# 04-SPDIF_IIC.net
KiCad netlist of a schematic drawn in Altium Designer
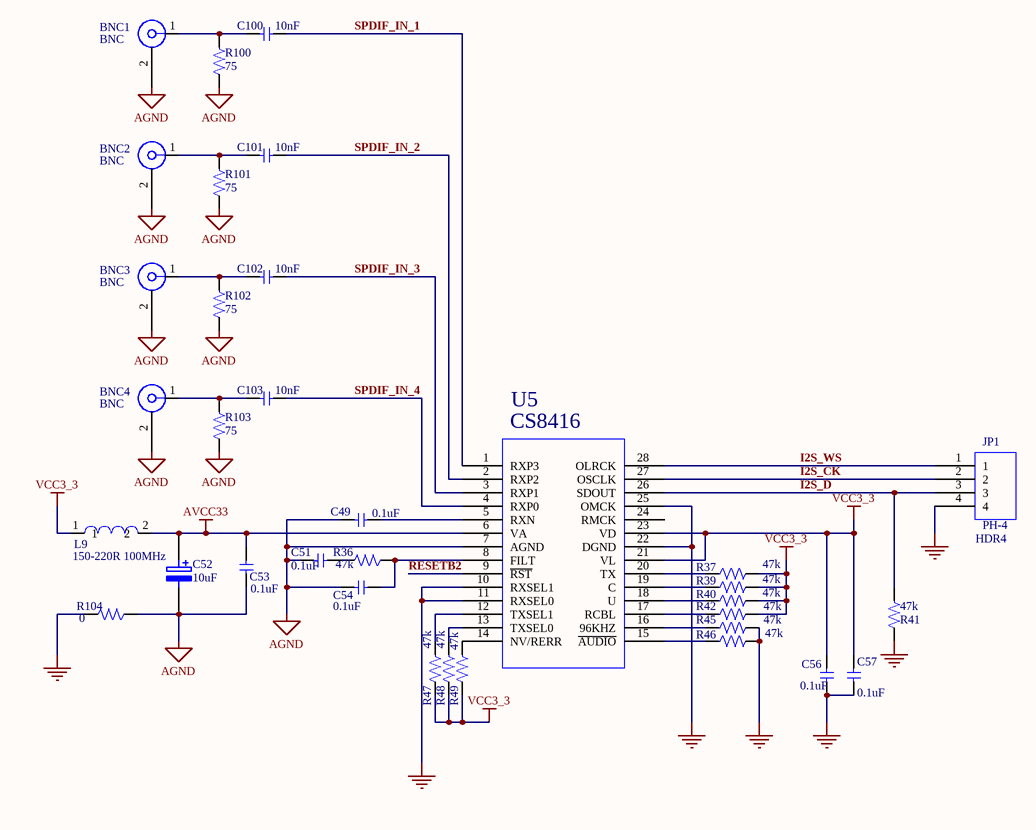
[diagram p0: 04-SPDIF_IIC.SchDoc]

(export (version "E")
  (design (tool "Eeschema 10.0.6"))
  (components
    (comp (ref "BNC1")
      (value "BNC")
      (footprint "RCA-101")
      (fields (field (name "SOURCE_PATH") "C:\\PROGRAM FILES\\印院出品\\CAPTURE 16.2\\LIBRARY\\CONNECTOR.OLB"))
      (libsource (lib "VIDEO_Demo_Kit_1") (part "BNC"))
    )
    (comp (ref "BNC2")
      (value "BNC")
      (footprint "RCA-101")
      (fields (field (name "SOURCE_PATH") "C:\\PROGRAM FILES\\印院出品\\CAPTURE 16.2\\LIBRARY\\CONNECTOR.OLB"))
      (libsource (lib "VIDEO_Demo_Kit_1") (part "BNC"))
    )
    (comp (ref "BNC3")
      (value "BNC")
      (footprint "RCA-101")
      (fields (field (name "SOURCE_PATH") "C:\\PROGRAM FILES\\印院出品\\CAPTURE 16.2\\LIBRARY\\CONNECTOR.OLB"))
      (libsource (lib "VIDEO_Demo_Kit_1") (part "BNC"))
    )
    (comp (ref "BNC4")
      (value "BNC")
      (footprint "RCA-101")
      (fields (field (name "SOURCE_PATH") "C:\\PROGRAM FILES\\印院出品\\CAPTURE 16.2\\LIBRARY\\CONNECTOR.OLB"))
      (libsource (lib "VIDEO_Demo_Kit_1") (part "BNC"))
    )
    (comp (ref "C49")
      (value "0.1uF")
      (footprint "C0603")
      (fields (field (name "VOLTAGE") "CMAX") (field (name "Comment") "C_2"))
      (libsource (lib "VIDEO_Demo_Kit_1") (part "C_2"))
    )
    (comp (ref "C51")
      (value "0.1uF")
      (footprint "C0603")
      (fields (field (name "VOLTAGE") "CMAX") (field (name "Comment") "C_2"))
      (libsource (lib "VIDEO_Demo_Kit_1") (part "C_2"))
    )
    (comp (ref "C52")
      (value "10uF")
      (footprint "3528-C")
      (description "Electrolytic Capacitor")
      (libsource (lib "*") (part "ELECTRO2"))
    )
    (comp (ref "C53")
      (value "0.1uF")
      (footprint "C0603")
      (fields (field (name "VOLTAGE") "CMAX") (field (name "Comment") "C_2"))
      (libsource (lib "VIDEO_Demo_Kit_1") (part "C_2"))
    )
    (comp (ref "C54")
      (value "0.1uF")
      (footprint "C0603")
      (fields (field (name "VOLTAGE") "CMAX") (field (name "Comment") "C_2"))
      (libsource (lib "VIDEO_Demo_Kit_1") (part "C_2"))
    )
    (comp (ref "C56")
      (value "0.1uF")
      (footprint "C0603")
      (fields (field (name "VOLTAGE") "CMAX") (field (name "Comment") "C_2"))
      (libsource (lib "VIDEO_Demo_Kit_1") (part "C_2"))
    )
    (comp (ref "C57")
      (value "0.1uF")
      (footprint "C0603")
      (fields (field (name "VOLTAGE") "CMAX") (field (name "Comment") "C_2"))
      (libsource (lib "VIDEO_Demo_Kit_1") (part "C_2"))
    )
    (comp (ref "C100")
      (value "10nF")
      (footprint "C0603")
      (fields (field (name "VOLTAGE") "CMAX") (field (name "Comment") "C_2"))
      (libsource (lib "VIDEO_Demo_Kit_1") (part "C_2"))
    )
    (comp (ref "C101")
      (value "10nF")
      (footprint "C0603")
      (fields (field (name "VOLTAGE") "CMAX") (field (name "Comment") "C_2"))
      (libsource (lib "VIDEO_Demo_Kit_1") (part "C_2"))
    )
    (comp (ref "C102")
      (value "10nF")
      (footprint "C0603")
      (fields (field (name "VOLTAGE") "CMAX") (field (name "Comment") "C_2"))
      (libsource (lib "VIDEO_Demo_Kit_1") (part "C_2"))
    )
    (comp (ref "C103")
      (value "10nF")
      (footprint "C0603")
      (fields (field (name "VOLTAGE") "CMAX") (field (name "Comment") "C_2"))
      (libsource (lib "VIDEO_Demo_Kit_1") (part "C_2"))
    )
    (comp (ref "JP1")
      (value "PH-4")
      (footprint "HDR4")
      (fields (field (name "PCB DECAL") "HDR4") (field (name "Comment") "HEADER_4"))
      (libsource (lib "*") (part "HEADER_4"))
    )
    (comp (ref "L9")
      (value "150-220R 100MHz")
      (footprint "0805-l")
      (fields (field (name "Comment") "INDUCTOR"))
      (libsource (lib "*") (part "INDUCTOR"))
    )
    (comp (ref "R36")
      (value "47k")
      (footprint "R0603")
      (fields (field (name "POWER") "RMAX") (field (name "VOLTAGE") "RVMAX") (field (name "Comment") "R_3"))
      (libsource (lib "VIDEO_Demo_Kit_1") (part "R_3"))
    )
    (comp (ref "R37")
      (value "47k")
      (footprint "R0603")
      (fields (field (name "POWER") "RMAX") (field (name "VOLTAGE") "RVMAX") (field (name "Comment") "R_3"))
      (libsource (lib "VIDEO_Demo_Kit_1") (part "R_3"))
    )
    (comp (ref "R39")
      (value "47k")
      (footprint "R0603")
      (fields (field (name "POWER") "RMAX") (field (name "VOLTAGE") "RVMAX") (field (name "Comment") "R_3"))
      (libsource (lib "VIDEO_Demo_Kit_1") (part "R_3"))
    )
    (comp (ref "R40")
      (value "47k")
      (footprint "R0603")
      (fields (field (name "POWER") "RMAX") (field (name "VOLTAGE") "RVMAX") (field (name "Comment") "R_3"))
      (libsource (lib "VIDEO_Demo_Kit_1") (part "R_3"))
    )
    (comp (ref "R41")
      (value "47k")
      (footprint "R0603")
      (fields (field (name "POWER") "RMAX") (field (name "VOLTAGE") "RVMAX") (field (name "Comment") "R_3"))
      (libsource (lib "VIDEO_Demo_Kit_1") (part "R_3"))
    )
    (comp (ref "R42")
      (value "47k")
      (footprint "R0603")
      (fields (field (name "POWER") "RMAX") (field (name "VOLTAGE") "RVMAX") (field (name "Comment") "R_3"))
      (libsource (lib "VIDEO_Demo_Kit_1") (part "R_3"))
    )
    (comp (ref "R45")
      (value "47k")
      (footprint "R0603")
      (fields (field (name "POWER") "RMAX") (field (name "VOLTAGE") "RVMAX") (field (name "Comment") "R_3"))
      (libsource (lib "VIDEO_Demo_Kit_1") (part "R_3"))
    )
    (comp (ref "R46")
      (value "47k")
      (footprint "R0603")
      (fields (field (name "POWER") "RMAX") (field (name "VOLTAGE") "RVMAX") (field (name "Comment") "R_3"))
      (libsource (lib "VIDEO_Demo_Kit_1") (part "R_3"))
    )
    (comp (ref "R47")
      (value "47k")
      (footprint "R0603")
      (fields (field (name "POWER") "RMAX") (field (name "VOLTAGE") "RVMAX") (field (name "Comment") "R_3"))
      (libsource (lib "VIDEO_Demo_Kit_1") (part "R_3"))
    )
    (comp (ref "R48")
      (value "47k")
      (footprint "R0603")
      (fields (field (name "POWER") "RMAX") (field (name "VOLTAGE") "RVMAX") (field (name "Comment") "R_3"))
      (libsource (lib "VIDEO_Demo_Kit_1") (part "R_3"))
    )
    (comp (ref "R49")
      (value "47k")
      (footprint "R0603")
      (fields (field (name "POWER") "RMAX") (field (name "VOLTAGE") "RVMAX") (field (name "Comment") "R_3"))
      (libsource (lib "VIDEO_Demo_Kit_1") (part "R_3"))
    )
    (comp (ref "R100")
      (value "75")
      (footprint "R0603")
      (fields (field (name "POWER") "RMAX") (field (name "VOLTAGE") "RVMAX") (field (name "Comment") "R_3"))
      (libsource (lib "VIDEO_Demo_Kit_1") (part "R_3"))
    )
    (comp (ref "R101")
      (value "75")
      (footprint "R0603")
      (fields (field (name "POWER") "RMAX") (field (name "VOLTAGE") "RVMAX") (field (name "Comment") "R_3"))
      (libsource (lib "VIDEO_Demo_Kit_1") (part "R_3"))
    )
    (comp (ref "R102")
      (value "75")
      (footprint "R0603")
      (fields (field (name "POWER") "RMAX") (field (name "VOLTAGE") "RVMAX") (field (name "Comment") "R_3"))
      (libsource (lib "VIDEO_Demo_Kit_1") (part "R_3"))
    )
    (comp (ref "R103")
      (value "75")
      (footprint "R0603")
      (fields (field (name "POWER") "RMAX") (field (name "VOLTAGE") "RVMAX") (field (name "Comment") "R_3"))
      (libsource (lib "VIDEO_Demo_Kit_1") (part "R_3"))
    )
    (comp (ref "R104")
      (value "0")
      (footprint "R0603")
      (fields (field (name "POWER") "RMAX") (field (name "VOLTAGE") "RVMAX") (field (name "Comment") "R_3"))
      (libsource (lib "VIDEO_Demo_Kit_1") (part "R_3"))
    )
    (comp (ref "U5")
      (value "CS8416")
      (footprint "TSSOP28")
      (fields (field (name "Comment") "ADG794_1"))
      (libsource (lib "*") (part "ADG794_1"))
    )
  )
  (nets
    (net (code "1") (name "/I2S_CK") (class "Default")
      (node (ref "JP1") (pin "2") (pinfunction "2_2") (pintype "passive"))
      (node (ref "U5") (pin "27") (pinfunction "OSCLK_27") (pintype "passive"))
    )
    (net (code "2") (name "/I2S_D") (class "Default")
      (node (ref "JP1") (pin "3") (pinfunction "3_3") (pintype "passive"))
      (node (ref "R41") (pin "1") (pinfunction "1_1") (pintype "passive"))
      (node (ref "U5") (pin "26") (pinfunction "SDOUT_26") (pintype "passive"))
    )
    (net (code "3") (name "/I2S_WS") (class "Default")
      (node (ref "JP1") (pin "1") (pinfunction "1_1") (pintype "passive"))
      (node (ref "U5") (pin "28") (pinfunction "OLRCK_28") (pintype "passive"))
    )
    (net (code "4") (name "/RESETB2") (class "Default")
      (node (ref "U5") (pin "9") (pinfunction "RST_9") (pintype "passive"))
    )
    (net (code "5") (name "/SPDIF_IN_1") (class "Default")
      (node (ref "C100") (pin "2") (pinfunction "2_2") (pintype "passive"))
      (node (ref "U5") (pin "1") (pinfunction "RXP3_1") (pintype "passive"))
    )
    (net (code "6") (name "/SPDIF_IN_2") (class "Default")
      (node (ref "C101") (pin "2") (pinfunction "2_2") (pintype "passive"))
      (node (ref "U5") (pin "2") (pinfunction "RXP2_2") (pintype "passive"))
    )
    (net (code "7") (name "/SPDIF_IN_3") (class "Default")
      (node (ref "C102") (pin "2") (pinfunction "2_2") (pintype "passive"))
      (node (ref "U5") (pin "3") (pinfunction "RXP1_3") (pintype "passive"))
    )
    (net (code "8") (name "/SPDIF_IN_4") (class "Default")
      (node (ref "C103") (pin "2") (pinfunction "2_2") (pintype "passive"))
      (node (ref "U5") (pin "4") (pinfunction "RXP0_4") (pintype "passive"))
    )
    (net (code "9") (name "AGND") (class "Default")
      (node (ref "BNC1") (pin "2") (pinfunction "SHIELD_2") (pintype "passive"))
      (node (ref "BNC2") (pin "2") (pinfunction "SHIELD_2") (pintype "passive"))
      (node (ref "BNC3") (pin "2") (pinfunction "SHIELD_2") (pintype "passive"))
      (node (ref "BNC4") (pin "2") (pinfunction "SHIELD_2") (pintype "passive"))
      (node (ref "C49") (pin "1") (pinfunction "1_1") (pintype "passive"))
      (node (ref "C51") (pin "1") (pinfunction "1_1") (pintype "passive"))
      (node (ref "C52") (pin "2") (pinfunction "2_2") (pintype "passive"))
      (node (ref "C53") (pin "1") (pinfunction "1_1") (pintype "passive"))
      (node (ref "C54") (pin "1") (pinfunction "1_1") (pintype "passive"))
      (node (ref "R100") (pin "2") (pinfunction "2_2") (pintype "passive"))
      (node (ref "R101") (pin "2") (pinfunction "2_2") (pintype "passive"))
      (node (ref "R102") (pin "2") (pinfunction "2_2") (pintype "passive"))
      (node (ref "R103") (pin "2") (pinfunction "2_2") (pintype "passive"))
      (node (ref "R104") (pin "1") (pinfunction "1_1") (pintype "passive"))
      (node (ref "U5") (pin "7") (pinfunction "AGND_7") (pintype "passive"))
    )
    (net (code "10") (name "AVCC33") (class "Default")
      (node (ref "C52") (pin "1") (pinfunction "1_1") (pintype "passive"))
      (node (ref "C53") (pin "2") (pinfunction "2_2") (pintype "passive"))
      (node (ref "L9") (pin "2") (pinfunction "2_2") (pintype "passive"))
      (node (ref "U5") (pin "6") (pinfunction "VA_6") (pintype "passive"))
    )
    (net (code "11") (name "GND") (class "Default")
      (node (ref "C56") (pin "1") (pinfunction "1_1") (pintype "passive"))
      (node (ref "C57") (pin "1") (pinfunction "1_1") (pintype "passive"))
      (node (ref "JP1") (pin "4") (pinfunction "4_4") (pintype "passive"))
      (node (ref "R104") (pin "2") (pinfunction "2_2") (pintype "passive"))
      (node (ref "R41") (pin "2") (pinfunction "2_2") (pintype "passive"))
      (node (ref "R45") (pin "2") (pinfunction "2_2") (pintype "passive"))
      (node (ref "R46") (pin "2") (pinfunction "2_2") (pintype "passive"))
      (node (ref "U5") (pin "10") (pinfunction "RXSEL1_10") (pintype "passive"))
      (node (ref "U5") (pin "11") (pinfunction "RXSEL0_11") (pintype "passive"))
      (node (ref "U5") (pin "22") (pinfunction "DGND_22") (pintype "passive"))
      (node (ref "U5") (pin "25") (pinfunction "OMCK_25") (pintype "passive"))
    )
    (net (code "12") (name "Net-(BNC1-CENTER)") (class "Default")
      (node (ref "BNC1") (pin "1") (pinfunction "CENTER_1") (pintype "passive"))
      (node (ref "C100") (pin "1") (pinfunction "1_1") (pintype "passive"))
      (node (ref "R100") (pin "1") (pinfunction "1_1") (pintype "passive"))
    )
    (net (code "13") (name "Net-(BNC2-CENTER)") (class "Default")
      (node (ref "BNC2") (pin "1") (pinfunction "CENTER_1") (pintype "passive"))
      (node (ref "C101") (pin "1") (pinfunction "1_1") (pintype "passive"))
      (node (ref "R101") (pin "1") (pinfunction "1_1") (pintype "passive"))
    )
    (net (code "14") (name "Net-(BNC3-CENTER)") (class "Default")
      (node (ref "BNC3") (pin "1") (pinfunction "CENTER_1") (pintype "passive"))
      (node (ref "C102") (pin "1") (pinfunction "1_1") (pintype "passive"))
      (node (ref "R102") (pin "1") (pinfunction "1_1") (pintype "passive"))
    )
    (net (code "15") (name "Net-(BNC4-CENTER)") (class "Default")
      (node (ref "BNC4") (pin "1") (pinfunction "CENTER_1") (pintype "passive"))
      (node (ref "C103") (pin "1") (pinfunction "1_1") (pintype "passive"))
      (node (ref "R103") (pin "1") (pinfunction "1_1") (pintype "passive"))
    )
    (net (code "16") (name "Net-(C51-Pad2)") (class "Default")
      (node (ref "C51") (pin "2") (pinfunction "2_2") (pintype "passive"))
      (node (ref "R36") (pin "2") (pinfunction "2_2") (pintype "passive"))
    )
    (net (code "17") (name "Net-(U5-96KHZ)") (class "Default")
      (node (ref "R45") (pin "1") (pinfunction "1_1") (pintype "passive"))
      (node (ref "U5") (pin "16") (pinfunction "96KHZ_16") (pintype "passive"))
    )
    (net (code "18") (name "Net-(U5-AUDIO)") (class "Default")
      (node (ref "R46") (pin "1") (pinfunction "1_1") (pintype "passive"))
      (node (ref "U5") (pin "15") (pinfunction "AUDIO_15") (pintype "passive"))
    )
    (net (code "19") (name "Net-(U5-C)") (class "Default")
      (node (ref "R39") (pin "1") (pinfunction "1_1") (pintype "passive"))
      (node (ref "U5") (pin "19") (pinfunction "C_19") (pintype "passive"))
    )
    (net (code "20") (name "Net-(U5-FILT)") (class "Default")
      (node (ref "C54") (pin "2") (pinfunction "2_2") (pintype "passive"))
      (node (ref "R36") (pin "1") (pinfunction "1_1") (pintype "passive"))
      (node (ref "U5") (pin "8") (pinfunction "FILT_8") (pintype "passive"))
    )
    (net (code "21") (name "Net-(U5-NV{slash}RERR)") (class "Default")
      (node (ref "R49") (pin "1") (pinfunction "1_1") (pintype "passive"))
      (node (ref "U5") (pin "14") (pinfunction "NV/RERR_14") (pintype "passive"))
    )
    (net (code "22") (name "Net-(U5-RCBL)") (class "Default")
      (node (ref "R42") (pin "1") (pinfunction "1_1") (pintype "passive"))
      (node (ref "U5") (pin "17") (pinfunction "RCBL_17") (pintype "passive"))
    )
    (net (code "23") (name "Net-(U5-RXN)") (class "Default")
      (node (ref "C49") (pin "2") (pinfunction "2_2") (pintype "passive"))
      (node (ref "U5") (pin "5") (pinfunction "RXN_5") (pintype "passive"))
    )
    (net (code "24") (name "Net-(U5-TX)") (class "Default")
      (node (ref "R37") (pin "1") (pinfunction "1_1") (pintype "passive"))
      (node (ref "U5") (pin "20") (pinfunction "TX_20") (pintype "passive"))
    )
    (net (code "25") (name "Net-(U5-TXSEL0)") (class "Default")
      (node (ref "R48") (pin "1") (pinfunction "1_1") (pintype "passive"))
      (node (ref "U5") (pin "13") (pinfunction "TXSEL0_13") (pintype "passive"))
    )
    (net (code "26") (name "Net-(U5-TXSEL1)") (class "Default")
      (node (ref "R47") (pin "1") (pinfunction "1_1") (pintype "passive"))
      (node (ref "U5") (pin "12") (pinfunction "TXSEL1_12") (pintype "passive"))
    )
    (net (code "27") (name "Net-(U5-U)") (class "Default")
      (node (ref "R40") (pin "1") (pinfunction "1_1") (pintype "passive"))
      (node (ref "U5") (pin "18") (pinfunction "U_18") (pintype "passive"))
    )
    (net (code "28") (name "VCC3_3") (class "Default")
      (node (ref "C56") (pin "2") (pinfunction "2_2") (pintype "passive"))
      (node (ref "C57") (pin "2") (pinfunction "2_2") (pintype "passive"))
      (node (ref "L9") (pin "1") (pinfunction "1_1") (pintype "passive"))
      (node (ref "R37") (pin "2") (pinfunction "2_2") (pintype "passive"))
      (node (ref "R39") (pin "2") (pinfunction "2_2") (pintype "passive"))
      (node (ref "R40") (pin "2") (pinfunction "2_2") (pintype "passive"))
      (node (ref "R42") (pin "2") (pinfunction "2_2") (pintype "passive"))
      (node (ref "R47") (pin "2") (pinfunction "2_2") (pintype "passive"))
      (node (ref "R48") (pin "2") (pinfunction "2_2") (pintype "passive"))
      (node (ref "R49") (pin "2") (pinfunction "2_2") (pintype "passive"))
      (node (ref "U5") (pin "21") (pinfunction "VL_21") (pintype "passive"))
      (node (ref "U5") (pin "23") (pinfunction "VD_23") (pintype "passive"))
    )
    (net (code "29") (name "unconnected-(U5-RMCK-Pad24)") (class "Default")
      (node (ref "U5") (pin "24") (pinfunction "RMCK_24") (pintype "passive"))
    )
  )
)
